# carte_ascenseur.net
KiCad netlist of a schematic drawn in EAGLE
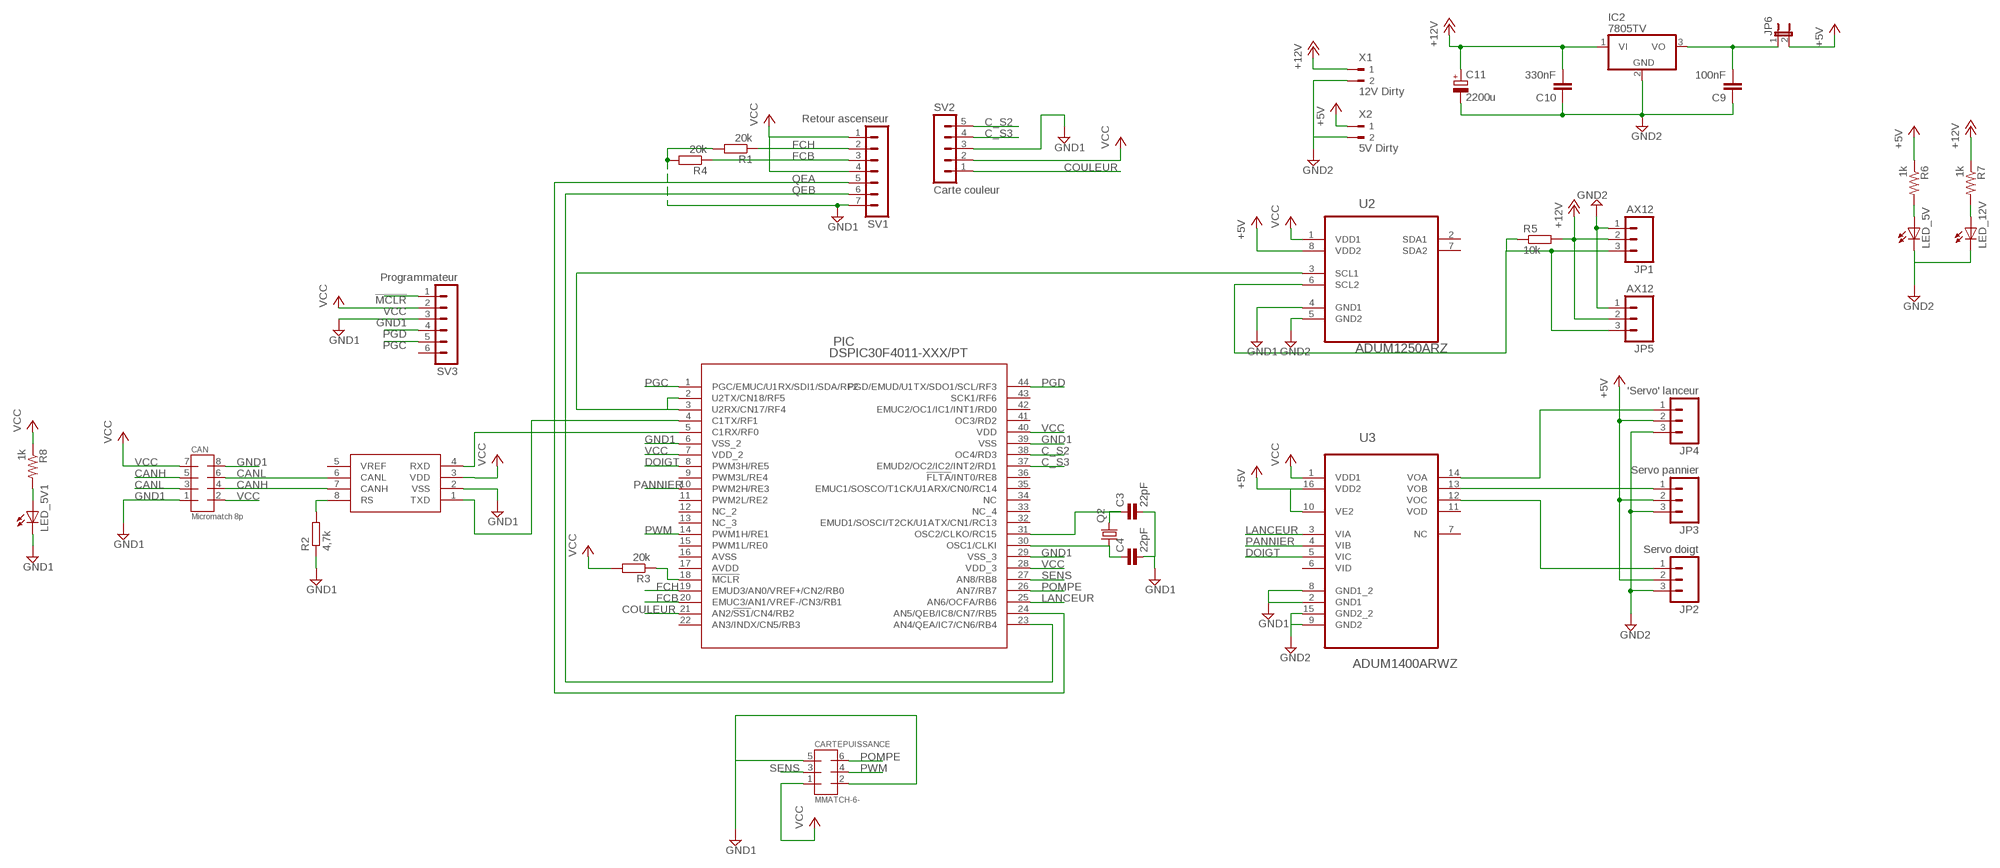
[diagram p0: schematic, sheet 1]

(export (version "E")
  (design (tool "Eeschema 10.0.6"))
  (components
    (comp (ref "C3")
      (value "22pF")
      (footprint "eagle-import:0805")
      (libsource (lib "eagle-import") (part "C0805"))
    )
    (comp (ref "C4")
      (value "22pF")
      (footprint "eagle-import:0805")
      (libsource (lib "eagle-import") (part "C0805"))
    )
    (comp (ref "C9")
      (value "100nF")
      (footprint "eagle-import:C0805")
      (libsource (lib "eagle-import") (part "C-EUC0805"))
    )
    (comp (ref "C10")
      (value "330nF")
      (footprint "eagle-import:C0805")
      (libsource (lib "eagle-import") (part "C-EUC0805"))
    )
    (comp (ref "C11")
      (value "2200u")
      (footprint "eagle-import:TT5D11")
      (libsource (lib "eagle-import") (part "CPOL-EUTT5D11"))
    )
    (comp (ref "CAN")
      (value "Micromatch 8p")
      (footprint "eagle-import:AMP-215079-8")
      (libsource (lib "eagle-import") (part "MMATCH-8-PTH"))
    )
    (comp (ref "CARTEPUISSANCE")
      (value "MMATCH-6-")
      (footprint "eagle-import:AMP-215079-6")
      (libsource (lib "eagle-import") (part "MMATCH-6-"))
    )
    (comp (ref "IC2")
      (value "7805TV")
      (footprint "eagle-import:TO220V")
      (libsource (lib "eagle-import") (part "78TV05"))
    )
    (comp (ref "JP1")
      (value "AX12")
      (footprint "eagle-import:MOLEX-1X3")
      (libsource (lib "eagle-import") (part "M03POLAR"))
    )
    (comp (ref "JP2")
      (value "Servo doigt")
      (footprint "eagle-import:1X03")
      (libsource (lib "eagle-import") (part "M03PTH"))
    )
    (comp (ref "JP3")
      (value "Servo pannier")
      (footprint "eagle-import:1X03")
      (libsource (lib "eagle-import") (part "M03PTH"))
    )
    (comp (ref "JP4")
      (value "'Servo' lanceur")
      (footprint "eagle-import:1X03")
      (libsource (lib "eagle-import") (part "M03PTH"))
    )
    (comp (ref "JP5")
      (value "AX12")
      (footprint "eagle-import:MOLEX-1X3")
      (libsource (lib "eagle-import") (part "M03POLAR"))
    )
    (comp (ref "JP6")
      (value "JP1E")
      (footprint "eagle-import:JP1")
      (libsource (lib "eagle-import") (part "JP1E"))
    )
    (comp (ref "LED_5V")
      (value "LEDCHIPLED_0805")
      (footprint "eagle-import:CHIPLED_0805")
      (libsource (lib "eagle-import") (part "LEDCHIPLED_0805"))
    )
    (comp (ref "LED_5V1")
      (value "LEDCHIPLED_0805")
      (footprint "eagle-import:CHIPLED_0805")
      (libsource (lib "eagle-import") (part "LEDCHIPLED_0805"))
    )
    (comp (ref "LED_12V")
      (value "LEDCHIPLED_0805")
      (footprint "eagle-import:CHIPLED_0805")
      (libsource (lib "eagle-import") (part "LEDCHIPLED_0805"))
    )
    (comp (ref "PIC")
      (value "DSPIC30F4011-XXX/PT")
      (footprint "eagle-import:TQFP44_MC")
      (libsource (lib "eagle-import") (part "DSPIC30F4011-XXX/PT"))
    )
    (comp (ref "Q2")
      (value "CRYSTALHC49S")
      (footprint "eagle-import:HC49_S")
      (libsource (lib "eagle-import") (part "CRYSTALHC49S"))
    )
    (comp (ref "R1")
      (value "20k")
      (footprint "eagle-import:M0805")
      (libsource (lib "eagle-import") (part "R-EU_M0805"))
    )
    (comp (ref "R2")
      (value "4,7k")
      (footprint "eagle-import:M0805")
      (libsource (lib "eagle-import") (part "R-EU_M0805"))
    )
    (comp (ref "R3")
      (value "20k")
      (footprint "eagle-import:M0805")
      (libsource (lib "eagle-import") (part "R-EU_M0805"))
    )
    (comp (ref "R4")
      (value "20k")
      (footprint "eagle-import:M0805")
      (libsource (lib "eagle-import") (part "R-EU_M0805"))
    )
    (comp (ref "R5")
      (value "10k")
      (footprint "eagle-import:M0805")
      (libsource (lib "eagle-import") (part "R-EU_M0805"))
    )
    (comp (ref "R6")
      (value "1k")
      (footprint "eagle-import:0805")
      (libsource (lib "eagle-import") (part "RESISTOR0805-RES"))
    )
    (comp (ref "R7")
      (value "1k")
      (footprint "eagle-import:0805")
      (libsource (lib "eagle-import") (part "RESISTOR0805-RES"))
    )
    (comp (ref "R8")
      (value "1k")
      (footprint "eagle-import:0805")
      (libsource (lib "eagle-import") (part "RESISTOR0805-RES"))
    )
    (comp (ref "SV1")
      (value "Retour ascenseur")
      (footprint "eagle-import:MA07-1")
      (libsource (lib "eagle-import") (part "MA07-1"))
    )
    (comp (ref "SV2")
      (value "Carte couleur")
      (footprint "eagle-import:MA05-1")
      (libsource (lib "eagle-import") (part "MA05-1"))
    )
    (comp (ref "SV3")
      (value "Programmateur")
      (footprint "eagle-import:MA06-1")
      (libsource (lib "eagle-import") (part "MA06-1"))
    )
    (comp (ref "U1")
      (value "MCP2551")
      (footprint "eagle-import:SO08")
      (libsource (lib "eagle-import") (part "MCP2551"))
    )
    (comp (ref "U2")
      (value "ADUM1250ARZ")
      (footprint "eagle-import:SOIC127P600X175-8N")
      (libsource (lib "eagle-import") (part "ADUM1250ARZ"))
    )
    (comp (ref "U3")
      (value "ADUM1400ARWZ")
      (footprint "eagle-import:SOIC127P1032X265-16N")
      (libsource (lib "eagle-import") (part "ADUM1400ARWZ"))
    )
    (comp (ref "X1")
      (value "12V Dirty")
      (footprint "eagle-import:90-2")
      (libsource (lib "eagle-import") (part "90-2"))
    )
    (comp (ref "X2")
      (value "5V Dirty")
      (footprint "eagle-import:90-2")
      (fields (field (name "OC_FARNELL") "unknown") (field (name "OC_NEWARK") "unknown"))
      (libsource (lib "eagle-import") (part "90-2"))
    )
  )
  (nets
    (net (code "1") (name "+5V") (class "Default")
      (node (ref "JP2") (pin "2") (pinfunction "2_2") (pintype "passive"))
      (node (ref "JP3") (pin "2") (pinfunction "2_2") (pintype "passive"))
      (node (ref "JP4") (pin "2") (pinfunction "2_2") (pintype "passive"))
      (node (ref "JP6") (pin "2") (pinfunction "2_2") (pintype "passive"))
      (node (ref "R6") (pin "1") (pinfunction "1_1") (pintype "passive"))
      (node (ref "U2") (pin "8") (pinfunction "VDD2_8") (pintype "power_in"))
      (node (ref "U3") (pin "10") (pinfunction "VE2_10") (pintype "input"))
      (node (ref "U3") (pin "16") (pinfunction "VDD2_16") (pintype "power_in"))
      (node (ref "X2") (pin "1") (pinfunction "1_1") (pintype "passive"))
    )
    (net (code "2") (name "+12V") (class "Default")
      (node (ref "C10") (pin "2") (pinfunction "2_2") (pintype "passive"))
      (node (ref "C11") (pin "+") (pinfunction "+_+") (pintype "passive"))
      (node (ref "IC2") (pin "1") (pinfunction "VI_1") (pintype "input"))
      (node (ref "JP1") (pin "2") (pinfunction "2_2") (pintype "passive"))
      (node (ref "JP5") (pin "2") (pinfunction "2_2") (pintype "passive"))
      (node (ref "R5") (pin "2") (pinfunction "2_2") (pintype "passive"))
      (node (ref "R7") (pin "1") (pinfunction "1_1") (pintype "passive"))
      (node (ref "X1") (pin "1") (pinfunction "1_1") (pintype "passive"))
    )
    (net (code "3") (name "/CANH") (class "Default")
      (node (ref "CAN") (pin "4") (pinfunction "4_4") (pintype "bidirectional"))
      (node (ref "CAN") (pin "5") (pinfunction "5_5") (pintype "bidirectional"))
      (node (ref "U1") (pin "7") (pinfunction "CANH_7") (pintype "bidirectional"))
    )
    (net (code "4") (name "/CANL") (class "Default")
      (node (ref "CAN") (pin "3") (pinfunction "3_3") (pintype "bidirectional"))
      (node (ref "CAN") (pin "6") (pinfunction "6_6") (pintype "bidirectional"))
      (node (ref "U1") (pin "6") (pinfunction "CANL_6") (pintype "bidirectional"))
    )
    (net (code "5") (name "/COULEUR") (class "Default")
      (node (ref "PIC") (pin "21") (pinfunction "AN2/~{SS1}/CN4/RB2_21") (pintype "passive"))
      (node (ref "SV2") (pin "1") (pinfunction "1_1") (pintype "passive"))
    )
    (net (code "6") (name "/C_S2") (class "Default")
      (node (ref "PIC") (pin "38") (pinfunction "OC4/RD3_38") (pintype "passive"))
      (node (ref "SV2") (pin "5") (pinfunction "5_5") (pintype "passive"))
    )
    (net (code "7") (name "/C_S3") (class "Default")
      (node (ref "PIC") (pin "37") (pinfunction "EMUD2/OC2/IC2/INT2/RD1_37") (pintype "passive"))
      (node (ref "SV2") (pin "4") (pinfunction "4_4") (pintype "passive"))
    )
    (net (code "8") (name "/DOIGT") (class "Default")
      (node (ref "PIC") (pin "8") (pinfunction "PWM3H/RE5_8") (pintype "passive"))
      (node (ref "U3") (pin "5") (pinfunction "VIC_5") (pintype "input"))
    )
    (net (code "9") (name "/FCB") (class "Default")
      (node (ref "PIC") (pin "20") (pinfunction "EMUC3/AN1/VREF-/CN3/RB1_20") (pintype "passive"))
      (node (ref "R4") (pin "1") (pinfunction "1_1") (pintype "passive"))
      (node (ref "SV1") (pin "3") (pinfunction "3_3") (pintype "passive"))
    )
    (net (code "10") (name "/FCH") (class "Default")
      (node (ref "PIC") (pin "19") (pinfunction "EMUD3/AN0/VREF+/CN2/RB0_19") (pintype "passive"))
      (node (ref "R1") (pin "1") (pinfunction "1_1") (pintype "passive"))
      (node (ref "SV1") (pin "2") (pinfunction "2_2") (pintype "passive"))
    )
    (net (code "11") (name "/LANCEUR") (class "Default")
      (node (ref "PIC") (pin "25") (pinfunction "AN6/OCFA/RB6_25") (pintype "passive"))
      (node (ref "U3") (pin "3") (pinfunction "VIA_3") (pintype "input"))
    )
    (net (code "12") (name "/PANNIER") (class "Default")
      (node (ref "PIC") (pin "10") (pinfunction "PWM2H/RE3_10") (pintype "passive"))
      (node (ref "U3") (pin "4") (pinfunction "VIB_4") (pintype "input"))
    )
    (net (code "13") (name "/PGC") (class "Default")
      (node (ref "PIC") (pin "1") (pinfunction "PGC/EMUC/U1RX/SDI1/SDA/RF2_1") (pintype "passive"))
      (node (ref "SV3") (pin "5") (pinfunction "5_5") (pintype "passive"))
    )
    (net (code "14") (name "/PGD") (class "Default")
      (node (ref "PIC") (pin "44") (pinfunction "PGD/EMUD/U1TX/SDO1/SCL/RF3_44") (pintype "passive"))
      (node (ref "SV3") (pin "4") (pinfunction "4_4") (pintype "passive"))
    )
    (net (code "15") (name "/POMPE") (class "Default")
      (node (ref "CARTEPUISSANCE") (pin "6") (pinfunction "8_6") (pintype "bidirectional"))
      (node (ref "PIC") (pin "26") (pinfunction "AN7/RB7_26") (pintype "passive"))
    )
    (net (code "16") (name "/PWM") (class "Default")
      (node (ref "CARTEPUISSANCE") (pin "4") (pinfunction "6_4") (pintype "bidirectional"))
      (node (ref "PIC") (pin "14") (pinfunction "PWM1H/RE1_14") (pintype "passive"))
    )
    (net (code "17") (name "/QEA") (class "Default")
      (node (ref "PIC") (pin "24") (pinfunction "AN5/QEB/IC8/CN7/RB5_24") (pintype "passive"))
      (node (ref "SV1") (pin "5") (pinfunction "5_5") (pintype "passive"))
    )
    (net (code "18") (name "/QEB") (class "Default")
      (node (ref "PIC") (pin "23") (pinfunction "AN4/QEA/IC7/CN6/RB4_23") (pintype "passive"))
      (node (ref "SV1") (pin "6") (pinfunction "6_6") (pintype "passive"))
    )
    (net (code "19") (name "/SENS") (class "Default")
      (node (ref "CARTEPUISSANCE") (pin "3") (pinfunction "5_3") (pintype "bidirectional"))
      (node (ref "PIC") (pin "27") (pinfunction "AN8/RB8_27") (pintype "passive"))
    )
    (net (code "20") (name "/~{MCLR}") (class "Default")
      (node (ref "PIC") (pin "18") (pinfunction "~{MCLR}_18") (pintype "passive"))
      (node (ref "R3") (pin "1") (pinfunction "1_1") (pintype "passive"))
      (node (ref "SV3") (pin "1") (pinfunction "1_1") (pintype "passive"))
    )
    (net (code "21") (name "GND1") (class "Default")
      (node (ref "C3") (pin "2") (pinfunction "P$2_2") (pintype "passive"))
      (node (ref "C4") (pin "2") (pinfunction "P$2_2") (pintype "passive"))
      (node (ref "CAN") (pin "1") (pinfunction "1_1") (pintype "bidirectional"))
      (node (ref "CAN") (pin "8") (pinfunction "8_8") (pintype "bidirectional"))
      (node (ref "CARTEPUISSANCE") (pin "2") (pinfunction "4_2") (pintype "bidirectional"))
      (node (ref "CARTEPUISSANCE") (pin "5") (pinfunction "7_5") (pintype "bidirectional"))
      (node (ref "LED_5V1") (pin "C") (pinfunction "C_C") (pintype "passive"))
      (node (ref "PIC") (pin "29") (pinfunction "VSS_3_29") (pintype "passive"))
      (node (ref "PIC") (pin "39") (pinfunction "VSS_39") (pintype "passive"))
      (node (ref "PIC") (pin "6") (pinfunction "VSS_2_6") (pintype "passive"))
      (node (ref "R1") (pin "2") (pinfunction "2_2") (pintype "passive"))
      (node (ref "R2") (pin "1") (pinfunction "1_1") (pintype "passive"))
      (node (ref "R4") (pin "2") (pinfunction "2_2") (pintype "passive"))
      (node (ref "SV1") (pin "7") (pinfunction "7_7") (pintype "passive"))
      (node (ref "SV2") (pin "3") (pinfunction "3_3") (pintype "passive"))
      (node (ref "SV3") (pin "3") (pinfunction "3_3") (pintype "passive"))
      (node (ref "U1") (pin "2") (pinfunction "VSS_2") (pintype "bidirectional"))
      (node (ref "U2") (pin "4") (pinfunction "GND1_4") (pintype "passive"))
      (node (ref "U3") (pin "2") (pinfunction "GND1_2") (pintype "passive"))
      (node (ref "U3") (pin "8") (pinfunction "GND1_2_8") (pintype "passive"))
    )
    (net (code "22") (name "GND2") (class "Default")
      (node (ref "C10") (pin "1") (pinfunction "1_1") (pintype "passive"))
      (node (ref "C11") (pin "-") (pinfunction "-_-") (pintype "passive"))
      (node (ref "C9") (pin "1") (pinfunction "1_1") (pintype "passive"))
      (node (ref "IC2") (pin "2") (pinfunction "GND_2") (pintype "passive"))
      (node (ref "JP1") (pin "1") (pinfunction "1_1") (pintype "passive"))
      (node (ref "JP2") (pin "3") (pinfunction "3_3") (pintype "passive"))
      (node (ref "JP3") (pin "3") (pinfunction "3_3") (pintype "passive"))
      (node (ref "JP4") (pin "3") (pinfunction "3_3") (pintype "passive"))
      (node (ref "JP5") (pin "1") (pinfunction "1_1") (pintype "passive"))
      (node (ref "LED_12V") (pin "C") (pinfunction "C_C") (pintype "passive"))
      (node (ref "LED_5V") (pin "C") (pinfunction "C_C") (pintype "passive"))
      (node (ref "U2") (pin "5") (pinfunction "GND2_5") (pintype "passive"))
      (node (ref "U3") (pin "15") (pinfunction "GND2_2_15") (pintype "passive"))
      (node (ref "U3") (pin "9") (pinfunction "GND2_9") (pintype "passive"))
      (node (ref "X1") (pin "2") (pinfunction "2_2") (pintype "passive"))
      (node (ref "X2") (pin "2") (pinfunction "2_2") (pintype "passive"))
    )
    (net (code "23") (name "Net-(C3-P$1)") (class "Default")
      (node (ref "C3") (pin "1") (pinfunction "P$1_1") (pintype "passive"))
      (node (ref "PIC") (pin "31") (pinfunction "OSC2/CLKO/RC15_31") (pintype "passive"))
      (node (ref "Q2") (pin "2") (pinfunction "2_2") (pintype "passive"))
    )
    (net (code "24") (name "Net-(C4-P$1)") (class "Default")
      (node (ref "C4") (pin "1") (pinfunction "P$1_1") (pintype "passive"))
      (node (ref "PIC") (pin "30") (pinfunction "OSC1/CLKI_30") (pintype "passive"))
      (node (ref "Q2") (pin "1") (pinfunction "1_1") (pintype "passive"))
    )
    (net (code "25") (name "Net-(IC2-VO)") (class "Default")
      (node (ref "C9") (pin "2") (pinfunction "2_2") (pintype "passive"))
      (node (ref "IC2") (pin "3") (pinfunction "VO_3") (pintype "passive"))
      (node (ref "JP6") (pin "1") (pinfunction "1_1") (pintype "passive"))
    )
    (net (code "26") (name "Net-(LED_5V-PadA)") (class "Default")
      (node (ref "LED_5V") (pin "A") (pinfunction "A_A") (pintype "passive"))
      (node (ref "R6") (pin "2") (pinfunction "2_2") (pintype "passive"))
    )
    (net (code "27") (name "Net-(LED_5V1-PadA)") (class "Default")
      (node (ref "LED_5V1") (pin "A") (pinfunction "A_A") (pintype "passive"))
      (node (ref "R8") (pin "2") (pinfunction "2_2") (pintype "passive"))
    )
    (net (code "28") (name "Net-(LED_12V-PadA)") (class "Default")
      (node (ref "LED_12V") (pin "A") (pinfunction "A_A") (pintype "passive"))
      (node (ref "R7") (pin "2") (pinfunction "2_2") (pintype "passive"))
    )
    (net (code "29") (name "Net-(PIC-C1RX{slash}RF0)") (class "Default")
      (node (ref "PIC") (pin "5") (pinfunction "C1RX/RF0_5") (pintype "passive"))
      (node (ref "U1") (pin "4") (pinfunction "RXD_4") (pintype "bidirectional"))
    )
    (net (code "30") (name "Net-(PIC-C1TX{slash}RF1)") (class "Default")
      (node (ref "PIC") (pin "4") (pinfunction "C1TX/RF1_4") (pintype "passive"))
      (node (ref "U1") (pin "1") (pinfunction "TXD_1") (pintype "bidirectional"))
    )
    (net (code "31") (name "Net-(PIC-U2RX{slash}CN17{slash}RF4)") (class "Default")
      (node (ref "PIC") (pin "2") (pinfunction "U2TX/CN18/RF5_2") (pintype "passive"))
      (node (ref "PIC") (pin "3") (pinfunction "U2RX/CN17/RF4_3") (pintype "passive"))
      (node (ref "U2") (pin "3") (pinfunction "SCL1_3") (pintype "input"))
    )
    (net (code "32") (name "Net-(U1-RS)") (class "Default")
      (node (ref "R2") (pin "2") (pinfunction "2_2") (pintype "passive"))
      (node (ref "U1") (pin "8") (pinfunction "RS_8") (pintype "bidirectional"))
    )
    (net (code "33") (name "Net-(U2-SCL2)") (class "Default")
      (node (ref "JP1") (pin "3") (pinfunction "3_3") (pintype "passive"))
      (node (ref "JP5") (pin "3") (pinfunction "3_3") (pintype "passive"))
      (node (ref "R5") (pin "1") (pinfunction "1_1") (pintype "passive"))
      (node (ref "U2") (pin "6") (pinfunction "SCL2_6") (pintype "input"))
    )
    (net (code "34") (name "Net-(U3-VOA)") (class "Default")
      (node (ref "JP4") (pin "1") (pinfunction "1_1") (pintype "passive"))
      (node (ref "U3") (pin "14") (pinfunction "VOA_14") (pintype "output"))
    )
    (net (code "35") (name "Net-(U3-VOB)") (class "Default")
      (node (ref "JP3") (pin "1") (pinfunction "1_1") (pintype "passive"))
      (node (ref "U3") (pin "13") (pinfunction "VOB_13") (pintype "output"))
    )
    (net (code "36") (name "Net-(U3-VOC)") (class "Default")
      (node (ref "JP2") (pin "1") (pinfunction "1_1") (pintype "passive"))
      (node (ref "U3") (pin "12") (pinfunction "VOC_12") (pintype "output"))
    )
    (net (code "37") (name "VCC") (class "Default")
      (node (ref "CAN") (pin "2") (pinfunction "2_2") (pintype "bidirectional"))
      (node (ref "CAN") (pin "7") (pinfunction "7_7") (pintype "bidirectional"))
      (node (ref "CARTEPUISSANCE") (pin "1") (pinfunction "3_1") (pintype "bidirectional"))
      (node (ref "PIC") (pin "28") (pinfunction "VDD_3_28") (pintype "passive"))
      (node (ref "PIC") (pin "40") (pinfunction "VDD_40") (pintype "passive"))
      (node (ref "PIC") (pin "7") (pinfunction "VDD_2_7") (pintype "passive"))
      (node (ref "R3") (pin "2") (pinfunction "2_2") (pintype "passive"))
      (node (ref "R8") (pin "1") (pinfunction "1_1") (pintype "passive"))
      (node (ref "SV1") (pin "1") (pinfunction "1_1") (pintype "passive"))
      (node (ref "SV1") (pin "4") (pinfunction "4_4") (pintype "passive"))
      (node (ref "SV2") (pin "2") (pinfunction "2_2") (pintype "passive"))
      (node (ref "SV3") (pin "2") (pinfunction "2_2") (pintype "passive"))
      (node (ref "U1") (pin "3") (pinfunction "VDD_3") (pintype "bidirectional"))
      (node (ref "U2") (pin "1") (pinfunction "VDD1_1") (pintype "power_in"))
      (node (ref "U3") (pin "1") (pinfunction "VDD1_1") (pintype "power_in"))
    )
    (net (code "38") (name "unconnected-(PIC-AN3{slash}INDX{slash}CN5{slash}RB3-Pad22)") (class "Default")
      (node (ref "PIC") (pin "22") (pinfunction "AN3/INDX/CN5/RB3_22") (pintype "passive"))
    )
    (net (code "39") (name "unconnected-(PIC-AVDD-Pad17)") (class "Default")
      (node (ref "PIC") (pin "17") (pinfunction "AVDD_17") (pintype "passive"))
    )
    (net (code "40") (name "unconnected-(PIC-AVSS-Pad16)") (class "Default")
      (node (ref "PIC") (pin "16") (pinfunction "AVSS_16") (pintype "passive"))
    )
    (net (code "41") (name "unconnected-(PIC-EMUC1{slash}SOSCO{slash}T1CK{slash}U1ARX{slash}CN0{slash}RC14-Pad35)") (class "Default")
      (node (ref "PIC") (pin "35") (pinfunction "EMUC1/SOSCO/T1CK/U1ARX/CN0/RC14_35") (pintype "passive"))
    )
    (net (code "42") (name "unconnected-(PIC-EMUC2{slash}OC1{slash}IC1{slash}INT1{slash}RD0-Pad42)") (class "Default")
      (node (ref "PIC") (pin "42") (pinfunction "EMUC2/OC1/IC1/INT1/RD0_42") (pintype "passive"))
    )
    (net (code "43") (name "unconnected-(PIC-EMUD1{slash}SOSCI{slash}T2CK{slash}U1ATX{slash}CN1{slash}RC13-Pad32)") (class "Default")
      (node (ref "PIC") (pin "32") (pinfunction "EMUD1/SOSCI/T2CK/U1ATX/CN1/RC13_32") (pintype "passive"))
    )
    (net (code "44") (name "unconnected-(PIC-NC-Pad34)") (class "Default")
      (node (ref "PIC") (pin "34") (pinfunction "NC_34") (pintype "passive"))
    )
    (net (code "45") (name "unconnected-(PIC-NC_2-Pad12)") (class "Default")
      (node (ref "PIC") (pin "12") (pinfunction "NC_2_12") (pintype "passive"))
    )
    (net (code "46") (name "unconnected-(PIC-NC_3-Pad13)") (class "Default")
      (node (ref "PIC") (pin "13") (pinfunction "NC_3_13") (pintype "passive"))
    )
    (net (code "47") (name "unconnected-(PIC-NC_4-Pad33)") (class "Default")
      (node (ref "PIC") (pin "33") (pinfunction "NC_4_33") (pintype "passive"))
    )
    (net (code "48") (name "unconnected-(PIC-OC3{slash}RD2-Pad41)") (class "Default")
      (node (ref "PIC") (pin "41") (pinfunction "OC3/RD2_41") (pintype "passive"))
    )
    (net (code "49") (name "unconnected-(PIC-PWM1L{slash}RE0-Pad15)") (class "Default")
      (node (ref "PIC") (pin "15") (pinfunction "PWM1L/RE0_15") (pintype "passive"))
    )
    (net (code "50") (name "unconnected-(PIC-PWM2L{slash}RE2-Pad11)") (class "Default")
      (node (ref "PIC") (pin "11") (pinfunction "PWM2L/RE2_11") (pintype "passive"))
    )
    (net (code "51") (name "unconnected-(PIC-PWM3L{slash}RE4-Pad9)") (class "Default")
      (node (ref "PIC") (pin "9") (pinfunction "PWM3L/RE4_9") (pintype "passive"))
    )
    (net (code "52") (name "unconnected-(PIC-SCK1{slash}RF6-Pad43)") (class "Default")
      (node (ref "PIC") (pin "43") (pinfunction "SCK1/RF6_43") (pintype "passive"))
    )
    (net (code "53") (name "unconnected-(PIC-~{FLTA}{slash}INT0{slash}RE8-Pad36)") (class "Default")
      (node (ref "PIC") (pin "36") (pinfunction "~{FLTA}/INT0/RE8_36") (pintype "passive"))
    )
    (net (code "54") (name "unconnected-(SV3-Pad6)") (class "Default")
      (node (ref "SV3") (pin "6") (pinfunction "6_6") (pintype "passive"))
    )
    (net (code "55") (name "unconnected-(U1-VREF-Pad5)") (class "Default")
      (node (ref "U1") (pin "5") (pinfunction "VREF_5") (pintype "bidirectional"))
    )
    (net (code "56") (name "unconnected-(U2-SDA1-Pad2)") (class "Default")
      (node (ref "U2") (pin "2") (pinfunction "SDA1_2") (pintype "bidirectional"))
    )
    (net (code "57") (name "unconnected-(U2-SDA2-Pad7)") (class "Default")
      (node (ref "U2") (pin "7") (pinfunction "SDA2_7") (pintype "bidirectional"))
    )
    (net (code "58") (name "unconnected-(U3-NC-Pad7)") (class "Default")
      (node (ref "U3") (pin "7") (pinfunction "NC_7") (pintype "no_connect"))
    )
    (net (code "59") (name "unconnected-(U3-VID-Pad6)") (class "Default")
      (node (ref "U3") (pin "6") (pinfunction "VID_6") (pintype "input"))
    )
    (net (code "60") (name "unconnected-(U3-VOD-Pad11)") (class "Default")
      (node (ref "U3") (pin "11") (pinfunction "VOD_11") (pintype "output"))
    )
  )
)
